# P1.net
KiCad netlist of a schematic drawn in Altium Designer
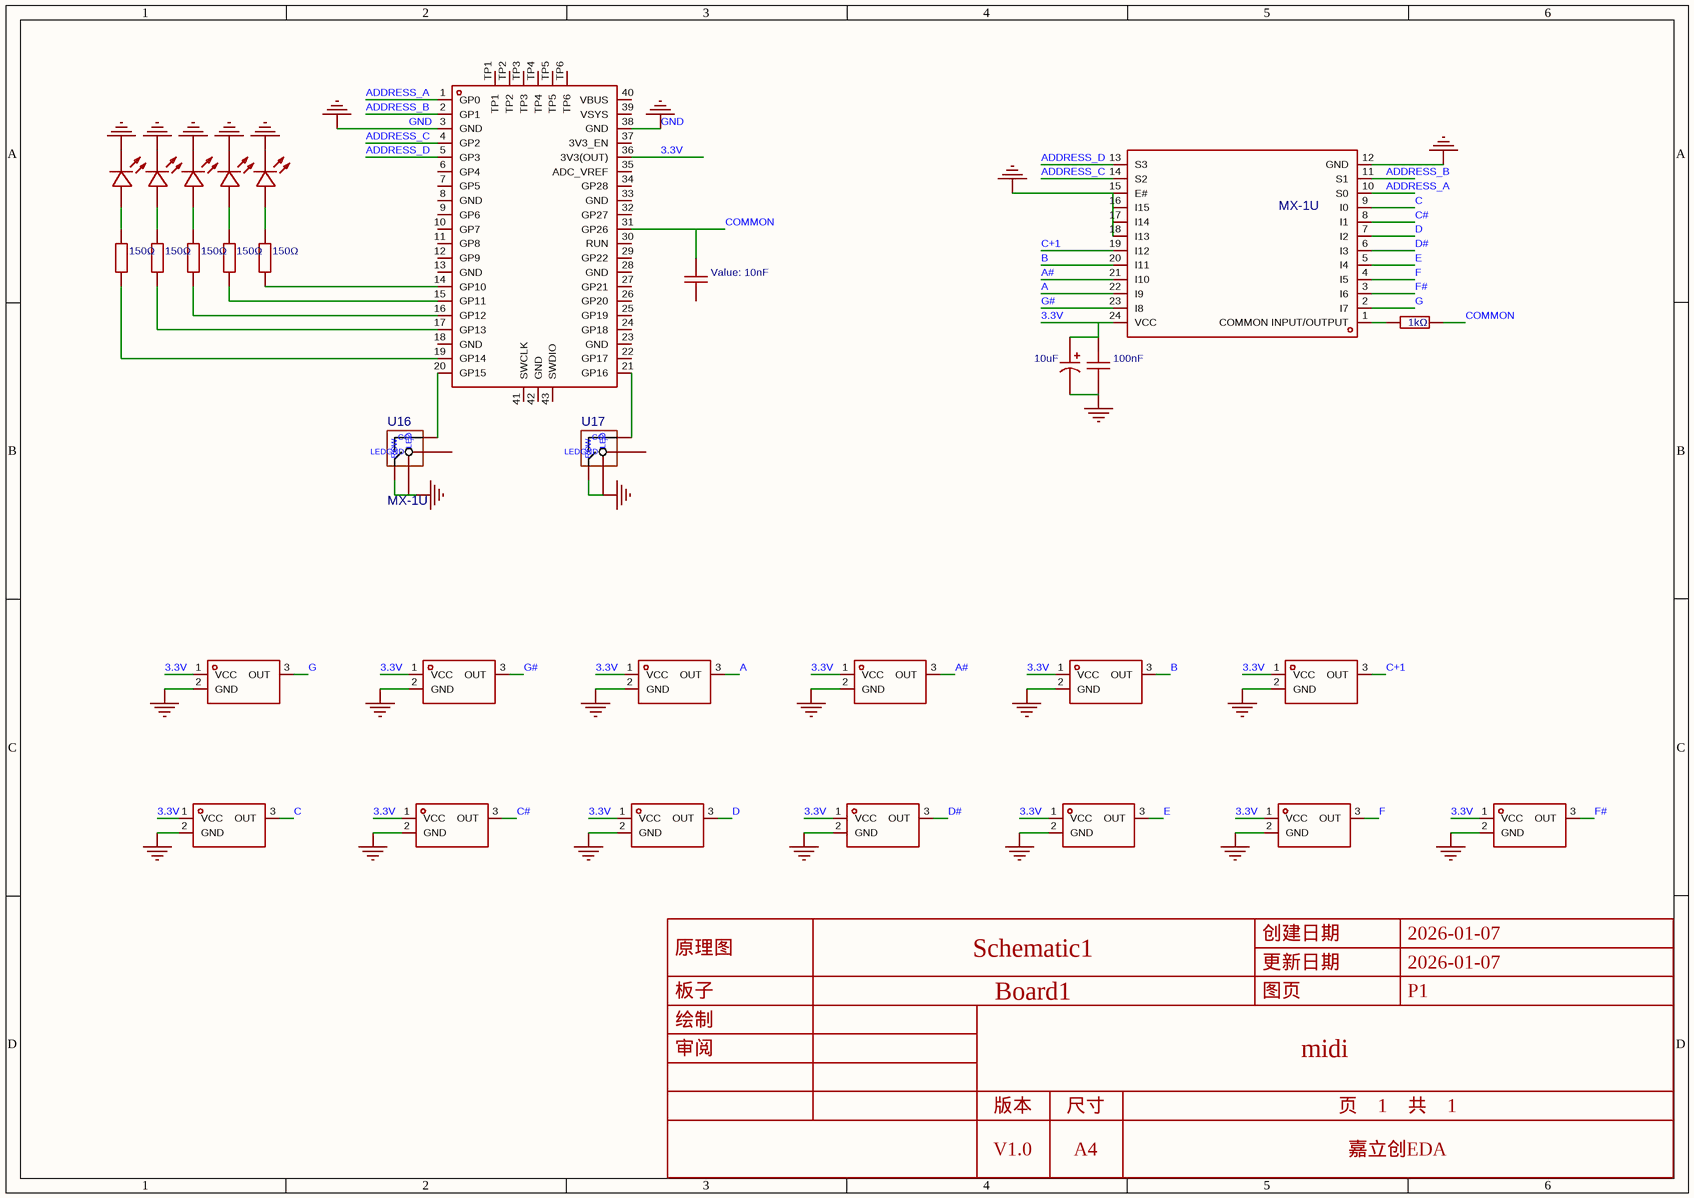
[diagram p0: P1.schdoc]

(export (version "E")
  (design (tool "Eeschema 10.0.6"))
  (components
    (comp (ref "C1")
      (value "10nF")
      (footprint "C0805")
      (description "容值:10nF;精度:±10%;额定电压:50V;温度系数:X7R;")
      (fields (field (name "MANUFACTURER") "SAMSUNG(三星)") (field (name "MANUFACTURERPART") "CL21B103KBANNNC"))
      (libsource (lib "altium-import") (part "root_1_CL21B103KBANNNC_"))
    )
    (comp (ref "C2")
      (value "100nF")
      (footprint "C0603")
      (description "容值:100nF;精度:±10%;额定电压:50V;温度系数:X7R;")
      (fields (field (name "MANUFACTURER") "HRE(芯声)") (field (name "MANUFACTURERPART") "CGA0603X7R104K500JT"))
      (libsource (lib "altium-import") (part "root_1_CGA0603X7R104K500JT_"))
    )
    (comp (ref "C3")
      (value "10uF")
      (footprint "CAP-SMD_BD5.0-L5.3-W5.3-LS6.0-FD")
      (description "容值:10uF;精度:±20%;额定电压:50V;纹波电流:18mA@120Hz;")
      (fields (field (name "MANUFACTURER PART") "JVJ50v10M5x5") (field (name "MANUFACTURER") "JIERR(捷而瑞)"))
      (libsource (lib "altium-import") (part "root_3_JVJ50v10M5x5_"))
    )
    (comp (ref "LED0")
      (value "NCD0603Y2")
      (footprint "LED0603-RD")
      (fields (field (name "MANUFACTURER") "国星光电"))
      (libsource (lib "altium-import") (part "root_3_NCD0603Y2_"))
    )
    (comp (ref "LED1")
      (value "NCD0603Y2")
      (footprint "LED0603-RD")
      (fields (field (name "MANUFACTURER") "国星光电"))
      (libsource (lib "altium-import") (part "root_3_NCD0603Y2_"))
    )
    (comp (ref "LED2")
      (value "NCD0603Y2")
      (footprint "LED0603-RD")
      (fields (field (name "MANUFACTURER") "国星光电"))
      (libsource (lib "altium-import") (part "root_3_NCD0603Y2_"))
    )
    (comp (ref "LED3")
      (value "NCD0603Y2")
      (footprint "LED0603-RD")
      (fields (field (name "MANUFACTURER") "国星光电"))
      (libsource (lib "altium-import") (part "root_3_NCD0603Y2_"))
    )
    (comp (ref "LED4")
      (value "NCD0603Y2")
      (footprint "LED0603-RD")
      (fields (field (name "MANUFACTURER") "国星光电"))
      (libsource (lib "altium-import") (part "root_3_NCD0603Y2_"))
    )
    (comp (ref "R1")
      (value "1kΩ")
      (footprint "R0603")
      (description "电阻类型:厚膜电阻;阻值:1kΩ;精度:±1%;功率:100mW;工作电压:75V;温度系数:±100ppm/℃;")
      (fields
        (field (name "MANUFACTURER") "UNI-ROYAL(厚声)")
        (field (name "MANUFACTURERPART") "0603WAF1001T5E")
      )
      (libsource (lib "altium-import") (part "root_0_0603WAF1001T5E_"))
    )
    (comp (ref "R2")
      (value "150Ω")
      (footprint "R0603")
      (description "电阻类型:厚膜电阻;阻值:150Ω;精度:±1%;功率:100mW;最大工作电压:75V;温度系数:±100ppm/℃;")
      (fields
        (field (name "MANUFACTURER") "UNI-ROYAL(厚声)")
        (field (name "MANUFACTURERPART") "0603WAF1500T5E")
      )
      (libsource (lib "altium-import") (part "root_1_0603WAF1500T5E_"))
    )
    (comp (ref "R3")
      (value "150Ω")
      (footprint "R0603")
      (description "电阻类型:厚膜电阻;阻值:150Ω;精度:±1%;功率:100mW;最大工作电压:75V;温度系数:±100ppm/℃;")
      (fields
        (field (name "MANUFACTURER") "UNI-ROYAL(厚声)")
        (field (name "MANUFACTURERPART") "0603WAF1500T5E")
      )
      (libsource (lib "altium-import") (part "root_1_0603WAF1500T5E_"))
    )
    (comp (ref "R4")
      (value "150Ω")
      (footprint "R0603")
      (description "电阻类型:厚膜电阻;阻值:150Ω;精度:±1%;功率:100mW;最大工作电压:75V;温度系数:±100ppm/℃;")
      (fields
        (field (name "MANUFACTURER") "UNI-ROYAL(厚声)")
        (field (name "MANUFACTURERPART") "0603WAF1500T5E")
      )
      (libsource (lib "altium-import") (part "root_1_0603WAF1500T5E_"))
    )
    (comp (ref "R5")
      (value "150Ω")
      (footprint "R0603")
      (description "电阻类型:厚膜电阻;阻值:150Ω;精度:±1%;功率:100mW;最大工作电压:75V;温度系数:±100ppm/℃;")
      (fields
        (field (name "MANUFACTURER") "UNI-ROYAL(厚声)")
        (field (name "MANUFACTURERPART") "0603WAF1500T5E")
      )
      (libsource (lib "altium-import") (part "root_1_0603WAF1500T5E_"))
    )
    (comp (ref "R6")
      (value "150Ω")
      (footprint "R0603")
      (description "电阻类型:厚膜电阻;阻值:150Ω;精度:±1%;功率:100mW;最大工作电压:75V;温度系数:±100ppm/℃;")
      (fields
        (field (name "MANUFACTURER") "UNI-ROYAL(厚声)")
        (field (name "MANUFACTURERPART") "0603WAF1500T5E")
      )
      (libsource (lib "altium-import") (part "root_1_0603WAF1500T5E_"))
    )
    (comp (ref "U1")
      (value "PICO")
      (footprint "COMM-SMD_L51.0-W21.0-P2.54_SC0916")
      (fields (field (name "MANUFACTURER") "Raspberry Pi(树莓派)"))
      (libsource (lib "altium-import") (part "root_0_PICO_"))
    )
    (comp (ref "U2")
      (value "CD74HC4067M96")
      (footprint "SOIC-24_L15.4-W7.5-P1.27-LS10.3-BL")
      (description "开关电路:-;通道数:-;导通电阻(Ron):70Ω;")
      (fields (field (name "MANUFACTURER") "TI(德州仪器)"))
      (libsource (lib "altium-import") (part "root_2_CD74HC4067M96_"))
    )
    (comp (ref "U3")
      (value "HAL403SO")
      (footprint "SOT-23-3_L2.9-W1.3-P1.90-LS2.4-BR-CW")
      (description "磁轴键盘线性霍尔元件，运动检测，摇杆")
      (fields (field (name "MANUFACTURER") "Hallwee(霍尔微电子)"))
      (libsource (lib "altium-import") (part "root_0_HAL403SO_"))
    )
    (comp (ref "U4")
      (value "HAL403SO")
      (footprint "SOT-23-3_L2.9-W1.3-P1.90-LS2.4-BR-CW")
      (description "磁轴键盘线性霍尔元件，运动检测，摇杆")
      (fields (field (name "MANUFACTURER") "Hallwee(霍尔微电子)"))
      (libsource (lib "altium-import") (part "root_0_HAL403SO_"))
    )
    (comp (ref "U5")
      (value "HAL403SO")
      (footprint "SOT-23-3_L2.9-W1.3-P1.90-LS2.4-BR-CW")
      (description "磁轴键盘线性霍尔元件，运动检测，摇杆")
      (fields (field (name "MANUFACTURER") "Hallwee(霍尔微电子)"))
      (libsource (lib "altium-import") (part "root_0_HAL403SO_"))
    )
    (comp (ref "U6")
      (value "HAL403SO")
      (footprint "SOT-23-3_L2.9-W1.3-P1.90-LS2.4-BR-CW")
      (description "磁轴键盘线性霍尔元件，运动检测，摇杆")
      (fields (field (name "MANUFACTURER") "Hallwee(霍尔微电子)"))
      (libsource (lib "altium-import") (part "root_0_HAL403SO_"))
    )
    (comp (ref "U7")
      (value "HAL403SO")
      (footprint "SOT-23-3_L2.9-W1.3-P1.90-LS2.4-BR-CW")
      (description "磁轴键盘线性霍尔元件，运动检测，摇杆")
      (fields (field (name "MANUFACTURER") "Hallwee(霍尔微电子)"))
      (libsource (lib "altium-import") (part "root_0_HAL403SO_"))
    )
    (comp (ref "U8")
      (value "HAL403SO")
      (footprint "SOT-23-3_L2.9-W1.3-P1.90-LS2.4-BR-CW")
      (description "磁轴键盘线性霍尔元件，运动检测，摇杆")
      (fields (field (name "MANUFACTURER") "Hallwee(霍尔微电子)"))
      (libsource (lib "altium-import") (part "root_0_HAL403SO_"))
    )
    (comp (ref "U9")
      (value "HAL403SO")
      (footprint "SOT-23-3_L2.9-W1.3-P1.90-LS2.4-BR-CW")
      (description "磁轴键盘线性霍尔元件，运动检测，摇杆")
      (fields (field (name "MANUFACTURER") "Hallwee(霍尔微电子)"))
      (libsource (lib "altium-import") (part "root_0_HAL403SO_"))
    )
    (comp (ref "U10")
      (value "HAL403SO")
      (footprint "SOT-23-3_L2.9-W1.3-P1.90-LS2.4-BR-CW")
      (description "磁轴键盘线性霍尔元件，运动检测，摇杆")
      (fields (field (name "MANUFACTURER") "Hallwee(霍尔微电子)"))
      (libsource (lib "altium-import") (part "root_0_HAL403SO_"))
    )
    (comp (ref "U11")
      (value "HAL403SO")
      (footprint "SOT-23-3_L2.9-W1.3-P1.90-LS2.4-BR-CW")
      (description "磁轴键盘线性霍尔元件，运动检测，摇杆")
      (fields (field (name "MANUFACTURER") "Hallwee(霍尔微电子)"))
      (libsource (lib "altium-import") (part "root_0_HAL403SO_"))
    )
    (comp (ref "U12")
      (value "HAL403SO")
      (footprint "SOT-23-3_L2.9-W1.3-P1.90-LS2.4-BR-CW")
      (description "磁轴键盘线性霍尔元件，运动检测，摇杆")
      (fields (field (name "MANUFACTURER") "Hallwee(霍尔微电子)"))
      (libsource (lib "altium-import") (part "root_0_HAL403SO_"))
    )
    (comp (ref "U13")
      (value "HAL403SO")
      (footprint "SOT-23-3_L2.9-W1.3-P1.90-LS2.4-BR-CW")
      (description "磁轴键盘线性霍尔元件，运动检测，摇杆")
      (fields (field (name "MANUFACTURER") "Hallwee(霍尔微电子)"))
      (libsource (lib "altium-import") (part "root_0_HAL403SO_"))
    )
    (comp (ref "U14")
      (value "HAL403SO")
      (footprint "SOT-23-3_L2.9-W1.3-P1.90-LS2.4-BR-CW")
      (description "磁轴键盘线性霍尔元件，运动检测，摇杆")
      (fields (field (name "MANUFACTURER") "Hallwee(霍尔微电子)"))
      (libsource (lib "altium-import") (part "root_0_HAL403SO_"))
    )
    (comp (ref "U15")
      (value "HAL403SO")
      (footprint "SOT-23-3_L2.9-W1.3-P1.90-LS2.4-BR-CW")
      (description "磁轴键盘线性霍尔元件，运动检测，摇杆")
      (fields (field (name "MANUFACTURER") "Hallwee(霍尔微电子)"))
      (libsource (lib "altium-import") (part "root_0_HAL403SO_"))
    )
    (comp (ref "U16")
      (value "MX-1U")
      (footprint "CHERRY MX 1U")
      (libsource (lib "altium-import") (part "root_2_MX-1U_"))
    )
    (comp (ref "U17")
      (value "MX-1U")
      (footprint "CHERRY MX 1U")
      (libsource (lib "altium-import") (part "root_2_MX-1U_"))
    )
  )
  (nets
    (net (code "1") (name "/3.3V") (class "Default")
      (node (ref "C2") (pin "2") (pinfunction "2_2") (pintype "passive"))
      (node (ref "C3") (pin "1") (pinfunction "1_1") (pintype "passive"))
      (node (ref "U1") (pin "36") (pinfunction "3V3(OUT)_36") (pintype "passive"))
      (node (ref "U10") (pin "1") (pinfunction "VCC_1") (pintype "passive"))
      (node (ref "U11") (pin "1") (pinfunction "VCC_1") (pintype "passive"))
      (node (ref "U12") (pin "1") (pinfunction "VCC_1") (pintype "passive"))
      (node (ref "U13") (pin "1") (pinfunction "VCC_1") (pintype "passive"))
      (node (ref "U14") (pin "1") (pinfunction "VCC_1") (pintype "passive"))
      (node (ref "U15") (pin "1") (pinfunction "VCC_1") (pintype "passive"))
      (node (ref "U2") (pin "24") (pinfunction "VCC_24") (pintype "passive"))
      (node (ref "U3") (pin "1") (pinfunction "VCC_1") (pintype "passive"))
      (node (ref "U4") (pin "1") (pinfunction "VCC_1") (pintype "passive"))
      (node (ref "U5") (pin "1") (pinfunction "VCC_1") (pintype "passive"))
      (node (ref "U6") (pin "1") (pinfunction "VCC_1") (pintype "passive"))
      (node (ref "U7") (pin "1") (pinfunction "VCC_1") (pintype "passive"))
      (node (ref "U8") (pin "1") (pinfunction "VCC_1") (pintype "passive"))
      (node (ref "U9") (pin "1") (pinfunction "VCC_1") (pintype "passive"))
    )
    (net (code "2") (name "/A") (class "Default")
      (node (ref "U13") (pin "3") (pinfunction "OUT_3") (pintype "passive"))
      (node (ref "U2") (pin "22") (pinfunction "I9_22") (pintype "passive"))
    )
    (net (code "3") (name "/A#") (class "Default")
      (node (ref "U14") (pin "3") (pinfunction "OUT_3") (pintype "passive"))
      (node (ref "U2") (pin "21") (pinfunction "I10_21") (pintype "passive"))
    )
    (net (code "4") (name "/ADDRESS_A") (class "Default")
      (node (ref "U1") (pin "1") (pinfunction "GP0_1") (pintype "passive"))
      (node (ref "U2") (pin "10") (pinfunction "S0_10") (pintype "passive"))
    )
    (net (code "5") (name "/ADDRESS_B") (class "Default")
      (node (ref "U1") (pin "2") (pinfunction "GP1_2") (pintype "passive"))
      (node (ref "U2") (pin "11") (pinfunction "S1_11") (pintype "passive"))
    )
    (net (code "6") (name "/ADDRESS_C") (class "Default")
      (node (ref "U1") (pin "4") (pinfunction "GP2_4") (pintype "passive"))
      (node (ref "U2") (pin "14") (pinfunction "S2_14") (pintype "passive"))
    )
    (net (code "7") (name "/ADDRESS_D") (class "Default")
      (node (ref "U1") (pin "5") (pinfunction "GP3_5") (pintype "passive"))
      (node (ref "U2") (pin "13") (pinfunction "S3_13") (pintype "passive"))
    )
    (net (code "8") (name "/B") (class "Default")
      (node (ref "U15") (pin "3") (pinfunction "OUT_3") (pintype "passive"))
      (node (ref "U2") (pin "20") (pinfunction "I11_20") (pintype "passive"))
    )
    (net (code "9") (name "/C") (class "Default")
      (node (ref "U2") (pin "9") (pinfunction "I0_9") (pintype "passive"))
      (node (ref "U3") (pin "3") (pinfunction "OUT_3") (pintype "passive"))
    )
    (net (code "10") (name "/C#") (class "Default")
      (node (ref "U2") (pin "8") (pinfunction "I1_8") (pintype "passive"))
      (node (ref "U4") (pin "3") (pinfunction "OUT_3") (pintype "passive"))
    )
    (net (code "11") (name "/C+1") (class "Default")
      (node (ref "U11") (pin "3") (pinfunction "OUT_3") (pintype "passive"))
      (node (ref "U2") (pin "19") (pinfunction "I12_19") (pintype "passive"))
    )
    (net (code "12") (name "/COMMON") (class "Default")
      (node (ref "C1") (pin "2") (pinfunction "2_2") (pintype "passive"))
      (node (ref "R1") (pin "2") (pinfunction "2_2") (pintype "passive"))
      (node (ref "U1") (pin "31") (pinfunction "GP26_31") (pintype "passive"))
    )
    (net (code "13") (name "/D") (class "Default")
      (node (ref "U2") (pin "7") (pinfunction "I2_7") (pintype "passive"))
      (node (ref "U5") (pin "3") (pinfunction "OUT_3") (pintype "passive"))
    )
    (net (code "14") (name "/D#") (class "Default")
      (node (ref "U2") (pin "6") (pinfunction "I3_6") (pintype "passive"))
      (node (ref "U6") (pin "3") (pinfunction "OUT_3") (pintype "passive"))
    )
    (net (code "15") (name "/E") (class "Default")
      (node (ref "U2") (pin "5") (pinfunction "I4_5") (pintype "passive"))
      (node (ref "U7") (pin "3") (pinfunction "OUT_3") (pintype "passive"))
    )
    (net (code "16") (name "/F") (class "Default")
      (node (ref "U2") (pin "4") (pinfunction "I5_4") (pintype "passive"))
      (node (ref "U8") (pin "3") (pinfunction "OUT_3") (pintype "passive"))
    )
    (net (code "17") (name "/F#") (class "Default")
      (node (ref "U2") (pin "3") (pinfunction "I6_3") (pintype "passive"))
      (node (ref "U9") (pin "3") (pinfunction "OUT_3") (pintype "passive"))
    )
    (net (code "18") (name "/G") (class "Default")
      (node (ref "U10") (pin "3") (pinfunction "OUT_3") (pintype "passive"))
      (node (ref "U2") (pin "2") (pinfunction "I7_2") (pintype "passive"))
    )
    (net (code "19") (name "/G#") (class "Default")
      (node (ref "U12") (pin "3") (pinfunction "OUT_3") (pintype "passive"))
      (node (ref "U2") (pin "23") (pinfunction "I8_23") (pintype "passive"))
    )
    (net (code "20") (name "GND") (class "Default")
      (node (ref "C2") (pin "1") (pinfunction "1_1") (pintype "passive"))
      (node (ref "C3") (pin "2") (pinfunction "2_2") (pintype "passive"))
      (node (ref "LED0") (pin "1") (pinfunction "K_1") (pintype "passive"))
      (node (ref "LED1") (pin "1") (pinfunction "K_1") (pintype "passive"))
      (node (ref "LED2") (pin "1") (pinfunction "K_1") (pintype "passive"))
      (node (ref "LED3") (pin "1") (pinfunction "K_1") (pintype "passive"))
      (node (ref "LED4") (pin "1") (pinfunction "K_1") (pintype "passive"))
      (node (ref "U1") (pin "3") (pinfunction "GND_3") (pintype "passive"))
      (node (ref "U1") (pin "38") (pinfunction "GND_38") (pintype "passive"))
      (node (ref "U10") (pin "2") (pinfunction "GND_2") (pintype "passive"))
      (node (ref "U11") (pin "2") (pinfunction "GND_2") (pintype "passive"))
      (node (ref "U12") (pin "2") (pinfunction "GND_2") (pintype "passive"))
      (node (ref "U13") (pin "2") (pinfunction "GND_2") (pintype "passive"))
      (node (ref "U14") (pin "2") (pinfunction "GND_2") (pintype "passive"))
      (node (ref "U15") (pin "2") (pinfunction "GND_2") (pintype "passive"))
      (node (ref "U16") (pin "LED") (pinfunction "LED_LED") (pintype "passive"))
      (node (ref "U16") (pin "ROW") (pinfunction "ROW_ROW") (pintype "passive"))
      (node (ref "U17") (pin "LED") (pinfunction "LED_LED") (pintype "passive"))
      (node (ref "U17") (pin "ROW") (pinfunction "ROW_ROW") (pintype "passive"))
      (node (ref "U2") (pin "12") (pinfunction "GND_12") (pintype "passive"))
      (node (ref "U2") (pin "15") (pinfunction "E#_15") (pintype "passive"))
      (node (ref "U2") (pin "16") (pinfunction "I15_16") (pintype "passive"))
      (node (ref "U2") (pin "17") (pinfunction "I14_17") (pintype "passive"))
      (node (ref "U2") (pin "18") (pinfunction "I13_18") (pintype "passive"))
      (node (ref "U3") (pin "2") (pinfunction "GND_2") (pintype "passive"))
      (node (ref "U4") (pin "2") (pinfunction "GND_2") (pintype "passive"))
      (node (ref "U5") (pin "2") (pinfunction "GND_2") (pintype "passive"))
      (node (ref "U6") (pin "2") (pinfunction "GND_2") (pintype "passive"))
      (node (ref "U7") (pin "2") (pinfunction "GND_2") (pintype "passive"))
      (node (ref "U8") (pin "2") (pinfunction "GND_2") (pintype "passive"))
      (node (ref "U9") (pin "2") (pinfunction "GND_2") (pintype "passive"))
    )
    (net (code "21") (name "Net-(LED0-A)") (class "Default")
      (node (ref "LED0") (pin "2") (pinfunction "A_2") (pintype "passive"))
      (node (ref "R2") (pin "2") (pinfunction "2_2") (pintype "passive"))
    )
    (net (code "22") (name "Net-(LED1-A)") (class "Default")
      (node (ref "LED1") (pin "2") (pinfunction "A_2") (pintype "passive"))
      (node (ref "R3") (pin "2") (pinfunction "2_2") (pintype "passive"))
    )
    (net (code "23") (name "Net-(LED2-A)") (class "Default")
      (node (ref "LED2") (pin "2") (pinfunction "A_2") (pintype "passive"))
      (node (ref "R4") (pin "2") (pinfunction "2_2") (pintype "passive"))
    )
    (net (code "24") (name "Net-(LED3-A)") (class "Default")
      (node (ref "LED3") (pin "2") (pinfunction "A_2") (pintype "passive"))
      (node (ref "R5") (pin "2") (pinfunction "2_2") (pintype "passive"))
    )
    (net (code "25") (name "Net-(LED4-A)") (class "Default")
      (node (ref "LED4") (pin "2") (pinfunction "A_2") (pintype "passive"))
      (node (ref "R6") (pin "2") (pinfunction "2_2") (pintype "passive"))
    )
    (net (code "26") (name "Net-(U1-GP10)") (class "Default")
      (node (ref "R2") (pin "1") (pinfunction "1_1") (pintype "passive"))
      (node (ref "U1") (pin "14") (pinfunction "GP10_14") (pintype "passive"))
    )
    (net (code "27") (name "Net-(U1-GP11)") (class "Default")
      (node (ref "R3") (pin "1") (pinfunction "1_1") (pintype "passive"))
      (node (ref "U1") (pin "15") (pinfunction "GP11_15") (pintype "passive"))
    )
    (net (code "28") (name "Net-(U1-GP12)") (class "Default")
      (node (ref "R4") (pin "1") (pinfunction "1_1") (pintype "passive"))
      (node (ref "U1") (pin "16") (pinfunction "GP12_16") (pintype "passive"))
    )
    (net (code "29") (name "Net-(U1-GP13)") (class "Default")
      (node (ref "R5") (pin "1") (pinfunction "1_1") (pintype "passive"))
      (node (ref "U1") (pin "17") (pinfunction "GP13_17") (pintype "passive"))
    )
    (net (code "30") (name "Net-(U1-GP14)") (class "Default")
      (node (ref "R6") (pin "1") (pinfunction "1_1") (pintype "passive"))
      (node (ref "U1") (pin "19") (pinfunction "GP14_19") (pintype "passive"))
    )
    (net (code "31") (name "Net-(U1-GP15)") (class "Default")
      (node (ref "U1") (pin "20") (pinfunction "GP15_20") (pintype "passive"))
      (node (ref "U16") (pin "COL") (pinfunction "COL_COL") (pintype "passive"))
    )
    (net (code "32") (name "Net-(U1-GP16)") (class "Default")
      (node (ref "U1") (pin "21") (pinfunction "GP16_21") (pintype "passive"))
      (node (ref "U17") (pin "COL") (pinfunction "COL_COL") (pintype "passive"))
    )
    (net (code "33") (name "Net-(U2-COMMON_INPUT{slash}OUTPUT)") (class "Default")
      (node (ref "R1") (pin "1") (pinfunction "1_1") (pintype "passive"))
      (node (ref "U2") (pin "1") (pinfunction "COMMON_INPUT/OUTPUT_1") (pintype "passive"))
    )
    (net (code "34") (name "unconnected-(C1-Pad1)") (class "Default")
      (node (ref "C1") (pin "1") (pinfunction "1_1") (pintype "passive"))
    )
    (net (code "35") (name "unconnected-(U1-3V3_EN-Pad37)") (class "Default")
      (node (ref "U1") (pin "37") (pinfunction "3V3_EN_37") (pintype "passive"))
    )
    (net (code "36") (name "unconnected-(U1-ADC_VREF-Pad35)") (class "Default")
      (node (ref "U1") (pin "35") (pinfunction "ADC_VREF_35") (pintype "passive"))
    )
    (net (code "37") (name "unconnected-(U1-GND-Pad8)") (class "Default")
      (node (ref "U1") (pin "8") (pinfunction "GND_8") (pintype "passive"))
    )
    (net (code "38") (name "unconnected-(U1-GND-Pad13)") (class "Default")
      (node (ref "U1") (pin "13") (pinfunction "GND_13") (pintype "passive"))
    )
    (net (code "39") (name "unconnected-(U1-GND-Pad18)") (class "Default")
      (node (ref "U1") (pin "18") (pinfunction "GND_18") (pintype "passive"))
    )
    (net (code "40") (name "unconnected-(U1-GND-Pad23)") (class "Default")
      (node (ref "U1") (pin "23") (pinfunction "GND_23") (pintype "passive"))
    )
    (net (code "41") (name "unconnected-(U1-GND-Pad28)") (class "Default")
      (node (ref "U1") (pin "28") (pinfunction "GND_28") (pintype "passive"))
    )
    (net (code "42") (name "unconnected-(U1-GND-Pad33)") (class "Default")
      (node (ref "U1") (pin "33") (pinfunction "GND_33") (pintype "passive"))
    )
    (net (code "43") (name "unconnected-(U1-GND-Pad42)") (class "Default")
      (node (ref "U1") (pin "42") (pinfunction "GND_42") (pintype "passive"))
    )
    (net (code "44") (name "unconnected-(U1-GP4-Pad6)") (class "Default")
      (node (ref "U1") (pin "6") (pinfunction "GP4_6") (pintype "passive"))
    )
    (net (code "45") (name "unconnected-(U1-GP5-Pad7)") (class "Default")
      (node (ref "U1") (pin "7") (pinfunction "GP5_7") (pintype "passive"))
    )
    (net (code "46") (name "unconnected-(U1-GP6-Pad9)") (class "Default")
      (node (ref "U1") (pin "9") (pinfunction "GP6_9") (pintype "passive"))
    )
    (net (code "47") (name "unconnected-(U1-GP7-Pad10)") (class "Default")
      (node (ref "U1") (pin "10") (pinfunction "GP7_10") (pintype "passive"))
    )
    (net (code "48") (name "unconnected-(U1-GP8-Pad11)") (class "Default")
      (node (ref "U1") (pin "11") (pinfunction "GP8_11") (pintype "passive"))
    )
    (net (code "49") (name "unconnected-(U1-GP9-Pad12)") (class "Default")
      (node (ref "U1") (pin "12") (pinfunction "GP9_12") (pintype "passive"))
    )
    (net (code "50") (name "unconnected-(U1-GP17-Pad22)") (class "Default")
      (node (ref "U1") (pin "22") (pinfunction "GP17_22") (pintype "passive"))
    )
    (net (code "51") (name "unconnected-(U1-GP18-Pad24)") (class "Default")
      (node (ref "U1") (pin "24") (pinfunction "GP18_24") (pintype "passive"))
    )
    (net (code "52") (name "unconnected-(U1-GP19-Pad25)") (class "Default")
      (node (ref "U1") (pin "25") (pinfunction "GP19_25") (pintype "passive"))
    )
    (net (code "53") (name "unconnected-(U1-GP20-Pad26)") (class "Default")
      (node (ref "U1") (pin "26") (pinfunction "GP20_26") (pintype "passive"))
    )
    (net (code "54") (name "unconnected-(U1-GP21-Pad27)") (class "Default")
      (node (ref "U1") (pin "27") (pinfunction "GP21_27") (pintype "passive"))
    )
    (net (code "55") (name "unconnected-(U1-GP22-Pad29)") (class "Default")
      (node (ref "U1") (pin "29") (pinfunction "GP22_29") (pintype "passive"))
    )
    (net (code "56") (name "unconnected-(U1-GP27-Pad32)") (class "Default")
      (node (ref "U1") (pin "32") (pinfunction "GP27_32") (pintype "passive"))
    )
    (net (code "57") (name "unconnected-(U1-GP28-Pad34)") (class "Default")
      (node (ref "U1") (pin "34") (pinfunction "GP28_34") (pintype "passive"))
    )
    (net (code "58") (name "unconnected-(U1-PadTP1)") (class "Default")
      (node (ref "U1") (pin "TP1") (pinfunction "TP1_TP1") (pintype "passive"))
    )
    (net (code "59") (name "unconnected-(U1-PadTP2)") (class "Default")
      (node (ref "U1") (pin "TP2") (pinfunction "TP2_TP2") (pintype "passive"))
    )
    (net (code "60") (name "unconnected-(U1-PadTP3)") (class "Default")
      (node (ref "U1") (pin "TP3") (pinfunction "TP3_TP3") (pintype "passive"))
    )
    (net (code "61") (name "unconnected-(U1-PadTP4)") (class "Default")
      (node (ref "U1") (pin "TP4") (pinfunction "TP4_TP4") (pintype "passive"))
    )
    (net (code "62") (name "unconnected-(U1-PadTP5)") (class "Default")
      (node (ref "U1") (pin "TP5") (pinfunction "TP5_TP5") (pintype "passive"))
    )
    (net (code "63") (name "unconnected-(U1-PadTP6)") (class "Default")
      (node (ref "U1") (pin "TP6") (pinfunction "TP6_TP6") (pintype "passive"))
    )
    (net (code "64") (name "unconnected-(U1-RUN-Pad30)") (class "Default")
      (node (ref "U1") (pin "30") (pinfunction "RUN_30") (pintype "passive"))
    )
    (net (code "65") (name "unconnected-(U1-SWCLK-Pad41)") (class "Default")
      (node (ref "U1") (pin "41") (pinfunction "SWCLK_41") (pintype "passive"))
    )
    (net (code "66") (name "unconnected-(U1-SWDIO-Pad43)") (class "Default")
      (node (ref "U1") (pin "43") (pinfunction "SWDIO_43") (pintype "passive"))
    )
    (net (code "67") (name "unconnected-(U1-VBUS-Pad40)") (class "Default")
      (node (ref "U1") (pin "40") (pinfunction "VBUS_40") (pintype "passive"))
    )
    (net (code "68") (name "unconnected-(U1-VSYS-Pad39)") (class "Default")
      (node (ref "U1") (pin "39") (pinfunction "VSYS_39") (pintype "passive"))
    )
    (net (code "69") (name "unconnected-(U16-PadLEDGND)") (class "Default")
      (node (ref "U16") (pin "LEDGND") (pinfunction "LEDGND_LEDGND") (pintype "passive"))
    )
    (net (code "70") (name "unconnected-(U17-PadLEDGND)") (class "Default")
      (node (ref "U17") (pin "LEDGND") (pinfunction "LEDGND_LEDGND") (pintype "passive"))
    )
  )
)
